# Breadboard_Power_Supply.net
KiCad netlist of a schematic drawn in EAGLE
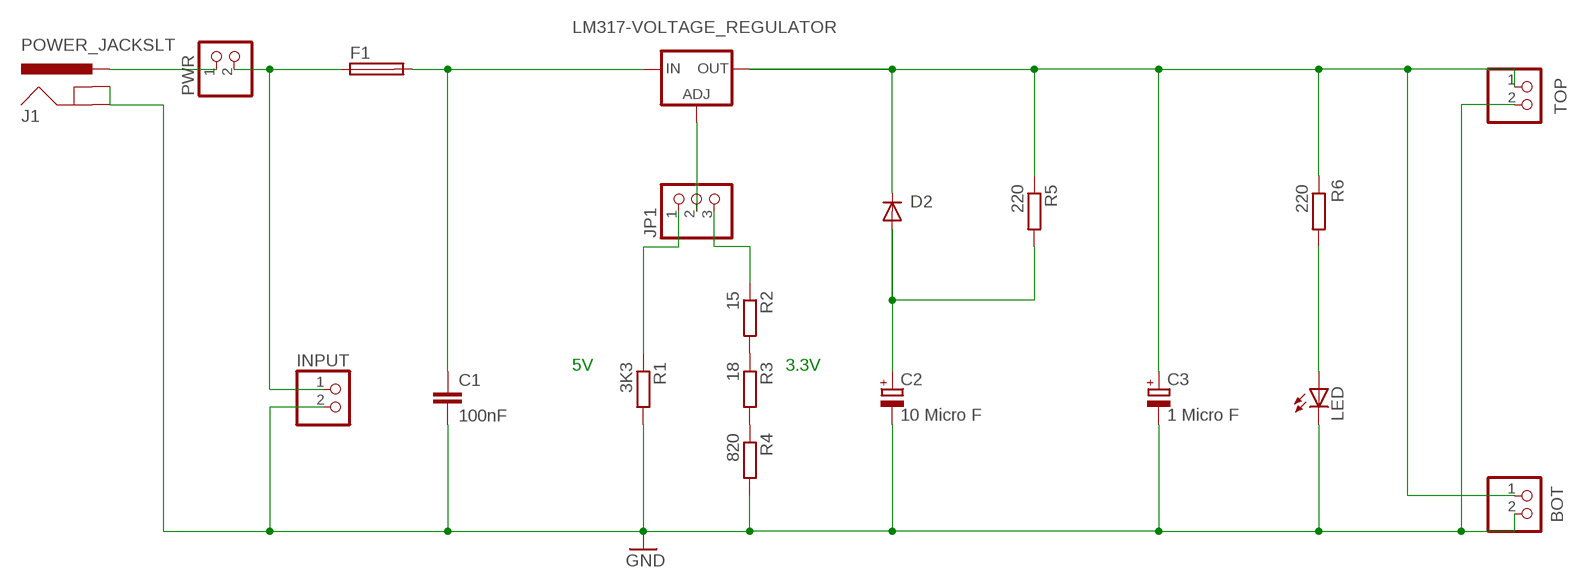
[diagram p0: schematic, sheet 1]

(export (version "E")
  (design (tool "Eeschema 10.0.6"))
  (components
    (comp (ref "BOT")
      (value "PINHD-1X2")
      (footprint "eagle-import:1X02")
      (libsource (lib "eagle-import") (part "PINHD-1X2"))
    )
    (comp (ref "C1")
      (value "100nF")
      (footprint "eagle-import:C025-030X050")
      (libsource (lib "eagle-import") (part "C-EU025-030X050"))
    )
    (comp (ref "C2")
      (value "10 Micro F")
      (footprint "eagle-import:E2-5")
      (libsource (lib "eagle-import") (part "CPOL-EUE2-5"))
    )
    (comp (ref "C3")
      (value "1 Micro F")
      (footprint "eagle-import:E2-5")
      (libsource (lib "eagle-import") (part "CPOL-EUE2-5"))
    )
    (comp (ref "D2")
      (value "1N4004")
      (footprint "eagle-import:DO41-10")
      (libsource (lib "eagle-import") (part "1N4004"))
    )
    (comp (ref "F1")
      (value "SH22,5A")
      (footprint "eagle-import:SH22,5A")
      (fields (field (name "MPN") "0031.7701.11"))
      (libsource (lib "eagle-import") (part "SH22,5A"))
    )
    (comp (ref "INPUT")
      (value "PINHD-1X2")
      (footprint "eagle-import:1X02")
      (libsource (lib "eagle-import") (part "PINHD-1X2"))
    )
    (comp (ref "J1")
      (value "POWER_JACKSLT")
      (footprint "eagle-import:POWER_JACK_SLOT")
      (libsource (lib "eagle-import") (part "POWER_JACKSLT"))
    )
    (comp (ref "JP1")
      (value "PINHD-1X3")
      (footprint "eagle-import:1X03")
      (libsource (lib "eagle-import") (part "PINHD-1X3"))
    )
    (comp (ref "LED")
      (value "TLLR4400")
      (footprint "eagle-import:LED3MM")
      (fields (field (name "MF") "VISHAY SEMICONDUCTOR"))
      (libsource (lib "eagle-import") (part "TLLR4400"))
    )
    (comp (ref "LM317-VOLTAGE_REGULATOR")
      (value "LM138-TS")
      (footprint "eagle-import:TO220S")
      (libsource (lib "eagle-import") (part "LM138-TS"))
    )
    (comp (ref "PWR")
      (value "PINHD-1X2")
      (footprint "eagle-import:1X02")
      (libsource (lib "eagle-import") (part "PINHD-1X2"))
    )
    (comp (ref "R1")
      (value "3K3")
      (footprint "eagle-import:0207_12")
      (libsource (lib "eagle-import") (part "R-EU_0207/12"))
    )
    (comp (ref "R2")
      (value "15")
      (footprint "eagle-import:0207_12")
      (libsource (lib "eagle-import") (part "R-EU_0207/12"))
    )
    (comp (ref "R3")
      (value "18")
      (footprint "eagle-import:0207_12")
      (libsource (lib "eagle-import") (part "R-EU_0207/12"))
    )
    (comp (ref "R4")
      (value "820")
      (footprint "eagle-import:0207_12")
      (libsource (lib "eagle-import") (part "R-EU_0207/12"))
    )
    (comp (ref "R5")
      (value "220")
      (footprint "eagle-import:0207_12")
      (libsource (lib "eagle-import") (part "R-EU_0207/12"))
    )
    (comp (ref "R6")
      (value "220")
      (footprint "eagle-import:0207_12")
      (libsource (lib "eagle-import") (part "R-EU_0207/12"))
    )
    (comp (ref "TOP")
      (value "PINHD-1X2")
      (footprint "eagle-import:1X02")
      (libsource (lib "eagle-import") (part "PINHD-1X2"))
    )
  )
  (nets
    (net (code "1") (name "GND") (class "Default")
      (node (ref "BOT") (pin "2") (pinfunction "2_2") (pintype "passive"))
      (node (ref "C1") (pin "2") (pinfunction "2_2") (pintype "passive"))
      (node (ref "C2") (pin "-") (pinfunction "-_-") (pintype "passive"))
      (node (ref "C3") (pin "-") (pinfunction "-_-") (pintype "passive"))
      (node (ref "INPUT") (pin "2") (pinfunction "2_2") (pintype "passive"))
      (node (ref "J1") (pin "GND@1") (pinfunction "GNDBREAK_GND@1") (pintype "bidirectional"))
      (node (ref "J1") (pin "GND@2") (pinfunction "GND_GND@2") (pintype "bidirectional"))
      (node (ref "LED") (pin "K") (pinfunction "C_K") (pintype "passive"))
      (node (ref "R1") (pin "2") (pinfunction "2_2") (pintype "passive"))
      (node (ref "R4") (pin "2") (pinfunction "2_2") (pintype "passive"))
      (node (ref "TOP") (pin "2") (pinfunction "2_2") (pintype "passive"))
    )
    (net (code "2") (name "Net-(C2-Pad+)") (class "Default")
      (node (ref "C2") (pin "+") (pinfunction "+_+") (pintype "passive"))
      (node (ref "D2") (pin "A") (pinfunction "A_A") (pintype "passive"))
      (node (ref "R5") (pin "2") (pinfunction "2_2") (pintype "passive"))
    )
    (net (code "3") (name "Net-(F1-Pad1)") (class "Default")
      (node (ref "F1") (pin "1") (pinfunction "1_1") (pintype "passive"))
      (node (ref "INPUT") (pin "1") (pinfunction "1_1") (pintype "passive"))
      (node (ref "PWR") (pin "2") (pinfunction "2_2") (pintype "passive"))
    )
    (net (code "4") (name "Net-(J1-PadPWR)") (class "Default")
      (node (ref "J1") (pin "PWR") (pinfunction "PWR_PWR") (pintype "bidirectional"))
      (node (ref "PWR") (pin "1") (pinfunction "1_1") (pintype "passive"))
    )
    (net (code "5") (name "Net-(JP1-Pad1)") (class "Default")
      (node (ref "JP1") (pin "1") (pinfunction "1_1") (pintype "passive"))
      (node (ref "R1") (pin "1") (pinfunction "1_1") (pintype "passive"))
    )
    (net (code "6") (name "Net-(JP1-Pad3)") (class "Default")
      (node (ref "JP1") (pin "3") (pinfunction "3_3") (pintype "passive"))
      (node (ref "R2") (pin "1") (pinfunction "1_1") (pintype "passive"))
    )
    (net (code "7") (name "Net-(LED-PadA)") (class "Default")
      (node (ref "LED") (pin "A") (pinfunction "A_A") (pintype "passive"))
      (node (ref "R6") (pin "2") (pinfunction "2_2") (pintype "passive"))
    )
    (net (code "8") (name "Net-(LM317-VOLTAGE_REGULATOR-ADJ)") (class "Default")
      (node (ref "JP1") (pin "2") (pinfunction "2_2") (pintype "passive"))
      (node (ref "LM317-VOLTAGE_REGULATOR") (pin "1") (pinfunction "ADJ_1") (pintype "input"))
    )
    (net (code "9") (name "Net-(LM317-VOLTAGE_REGULATOR-IN)") (class "Default")
      (node (ref "C1") (pin "1") (pinfunction "1_1") (pintype "passive"))
      (node (ref "F1") (pin "2") (pinfunction "2_2") (pintype "passive"))
      (node (ref "LM317-VOLTAGE_REGULATOR") (pin "3") (pinfunction "IN_3") (pintype "input"))
    )
    (net (code "10") (name "Net-(LM317-VOLTAGE_REGULATOR-OUT)") (class "Default")
      (node (ref "BOT") (pin "1") (pinfunction "1_1") (pintype "passive"))
      (node (ref "C3") (pin "+") (pinfunction "+_+") (pintype "passive"))
      (node (ref "D2") (pin "C") (pinfunction "C_C") (pintype "passive"))
      (node (ref "LM317-VOLTAGE_REGULATOR") (pin "2") (pinfunction "OUT_2") (pintype "passive"))
      (node (ref "R5") (pin "1") (pinfunction "1_1") (pintype "passive"))
      (node (ref "R6") (pin "1") (pinfunction "1_1") (pintype "passive"))
      (node (ref "TOP") (pin "1") (pinfunction "1_1") (pintype "passive"))
    )
    (net (code "11") (name "Net-(R2-Pad2)") (class "Default")
      (node (ref "R2") (pin "2") (pinfunction "2_2") (pintype "passive"))
      (node (ref "R3") (pin "1") (pinfunction "1_1") (pintype "passive"))
    )
    (net (code "12") (name "Net-(R3-Pad2)") (class "Default")
      (node (ref "R3") (pin "2") (pinfunction "2_2") (pintype "passive"))
      (node (ref "R4") (pin "1") (pinfunction "1_1") (pintype "passive"))
    )
  )
)
